# interface.net
KiCad netlist of a schematic drawn in Altium Designer
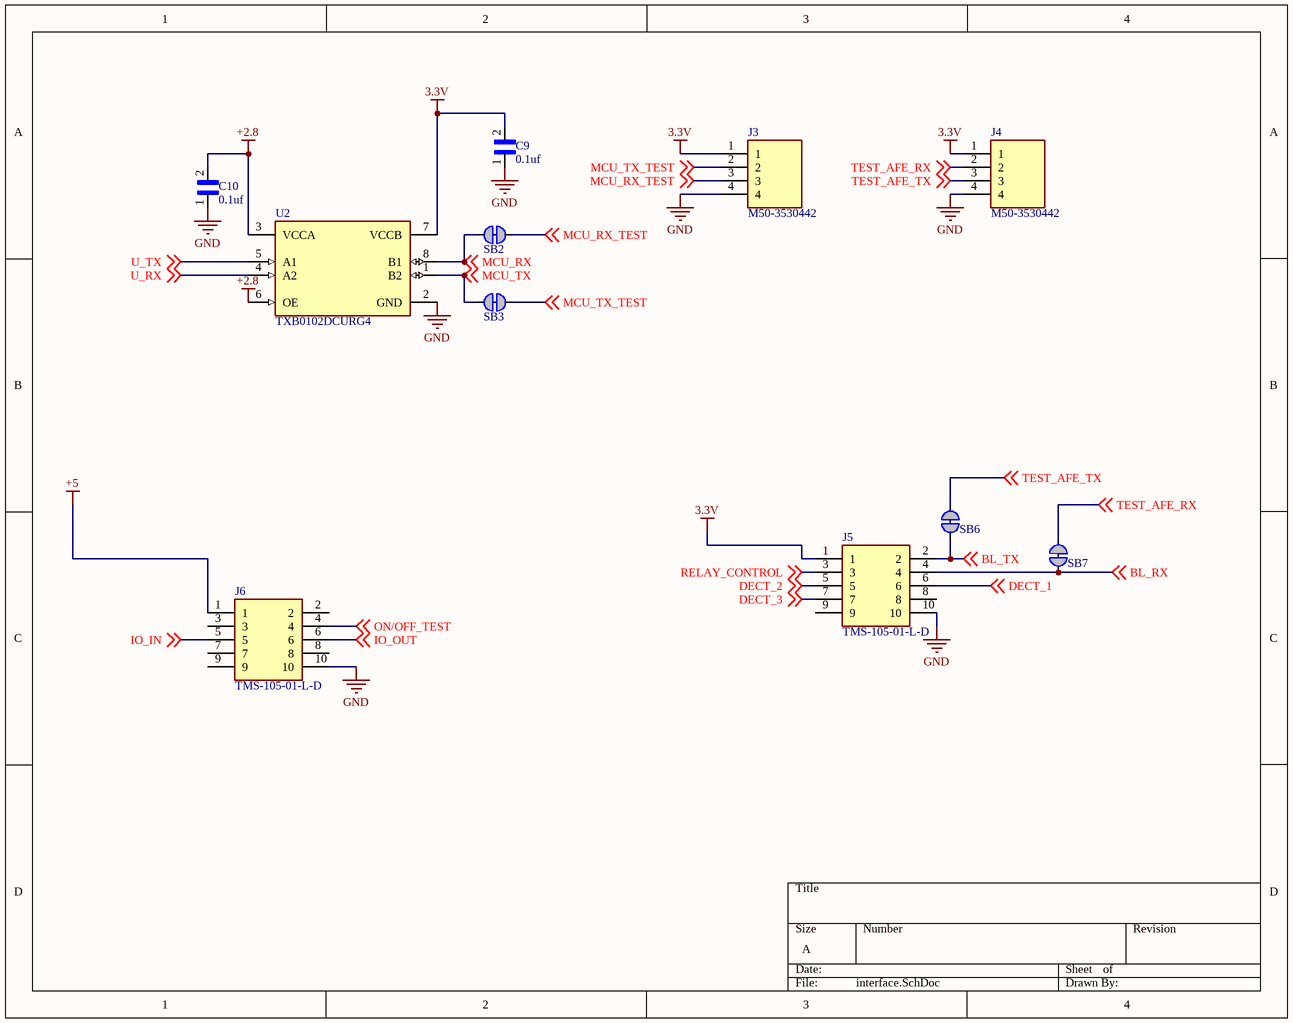
[diagram p0: interface.SchDoc]

(export (version "E")
  (design (tool "Eeschema 10.0.6"))
  (components
    (comp (ref "C9")
      (value "0.1uf")
      (footprint "CAPC1608X90N")
      (description "Cap Ceramic 0.1uF 25V Y5V -20% to 80% SMD 0603 85C T/R")
      (fields (field (name "MP") "06033G104ZAT4A") (field (name "MF") "{'manufacturer': u'AVX'}"))
      (libsource (lib "chargebot_alpha") (part "06033G104ZAT4A"))
    )
    (comp (ref "C10")
      (value "0.1uf")
      (footprint "CAPC1608X90N")
      (description "Cap Ceramic 0.1uF 25V Y5V -20% to 80% SMD 0603 85C T/R")
      (fields (field (name "MP") "06033G104ZAT4A") (field (name "MF") "{'manufacturer': u'AVX'}"))
      (libsource (lib "chargebot_alpha") (part "06033G104ZAT4A"))
    )
    (comp (ref "J3")
      (value "M50-3530442")
      (footprint "mouser_layout_lib:HDRV4W40P0X127_1X4_508X210X420P")
      (description "Connector")
      (fields (field (name "MOUSER PART NUMBER") "855-M50-3530442"))
      (libsource (lib "*") (part "M50-3530442"))
    )
    (comp (ref "J4")
      (value "M50-3530442")
      (footprint "mouser_layout_lib:HDRV4W40P0X127_1X4_508X210X420P")
      (description "Connector")
      (fields (field (name "MOUSER PART NUMBER") "855-M50-3530442"))
      (libsource (lib "*") (part "M50-3530442"))
    )
    (comp (ref "J5")
      (value "TMS-105-01-L-D")
      (footprint "mouser_layout_lib:HDRV10W51P254X127_2X5_635X498X838P")
      (description "Connector")
      (fields (field (name "MOUSER PART NUMBER") "200-TMS10501LD"))
      (libsource (lib "*") (part "TMS-105-01-L-D"))
    )
    (comp (ref "J6")
      (value "TMS-105-01-L-D")
      (footprint "mouser_layout_lib:HDRV10W51P254X127_2X5_635X498X838P")
      (description "Connector")
      (fields (field (name "MOUSER PART NUMBER") "200-TMS10501LD"))
      (libsource (lib "*") (part "TMS-105-01-L-D"))
    )
    (comp (ref "SB2")
      (value "Solderbridge")
      (footprint "SOLDERBRIDGE_SHORTED")
      (description "Shorted Solderbridge")
      (fields
        (field (name "PART NUMBER") "Solderbridge Shorted")
        (field (name "PUBLISHER") "Nordic Semiconductor")
      )
      (libsource (lib "apollo2-amaph1kk-kbr-brd") (part "SOLDERBRIDGE_SHORTED"))
    )
    (comp (ref "SB3")
      (value "Solderbridge")
      (footprint "SOLDERBRIDGE_SHORTED")
      (description "Shorted Solderbridge")
      (fields
        (field (name "PART NUMBER") "Solderbridge Shorted")
        (field (name "PUBLISHER") "Nordic Semiconductor")
      )
      (libsource (lib "apollo2-amaph1kk-kbr-brd") (part "SOLDERBRIDGE_SHORTED"))
    )
    (comp (ref "SB6")
      (value "Solderbridge")
      (footprint "SOLDERBRIDGE_SHORTED")
      (description "Shorted Solderbridge")
      (fields
        (field (name "PART NUMBER") "Solderbridge Shorted")
        (field (name "PUBLISHER") "Nordic Semiconductor")
      )
      (libsource (lib "apollo2-amaph1kk-kbr-brd") (part "SOLDERBRIDGE_SHORTED"))
    )
    (comp (ref "SB7")
      (value "Solderbridge")
      (footprint "SOLDERBRIDGE_SHORTED")
      (description "Shorted Solderbridge")
      (fields
        (field (name "PART NUMBER") "Solderbridge Shorted")
        (field (name "PUBLISHER") "Nordic Semiconductor")
      )
      (libsource (lib "apollo2-amaph1kk-kbr-brd") (part "SOLDERBRIDGE_SHORTED"))
    )
    (comp (ref "U2")
      (value "TXB0102DCURG4")
      (footprint "SOP50P310X90-8N")
      (description "IC TRNSLTR BIDIRECTIONAL US8")
      (libsource (lib "chargebot_alpha") (part "e5aacda1e23edf748dee3cec588ab45"))
    )
  )
  (nets
    (net (code "1") (name "+2.8") (class "Default")
      (node (ref "C10") (pin "2") (pinfunction "2_2") (pintype "passive"))
      (node (ref "U2") (pin "3") (pinfunction "VCCA_3") (pintype "passive"))
      (node (ref "U2") (pin "6") (pinfunction "OE_6") (pintype "input"))
    )
    (net (code "2") (name "+5") (class "Default")
      (node (ref "J6") (pin "1") (pinfunction "1_1") (pintype "passive"))
    )
    (net (code "3") (name "3.3V") (class "Default")
      (node (ref "C9") (pin "2") (pinfunction "2_2") (pintype "passive"))
      (node (ref "J3") (pin "1") (pinfunction "1_1") (pintype "passive"))
      (node (ref "J4") (pin "1") (pinfunction "1_1") (pintype "passive"))
      (node (ref "J5") (pin "1") (pinfunction "1_1") (pintype "passive"))
      (node (ref "U2") (pin "7") (pinfunction "VCCB_7") (pintype "passive"))
    )
    (net (code "4") (name "BL_RX") (class "Default")
      (node (ref "J5") (pin "4") (pinfunction "4_4") (pintype "passive"))
      (node (ref "SB7") (pin "2") (pinfunction "1_2") (pintype "passive"))
    )
    (net (code "5") (name "BL_TX") (class "Default")
      (node (ref "J5") (pin "2") (pinfunction "2_2") (pintype "passive"))
      (node (ref "SB6") (pin "1") (pinfunction "0_1") (pintype "passive"))
    )
    (net (code "6") (name "DECT_1") (class "Default")
      (node (ref "J5") (pin "6") (pinfunction "6_6") (pintype "passive"))
    )
    (net (code "7") (name "DECT_2") (class "Default")
      (node (ref "J5") (pin "5") (pinfunction "5_5") (pintype "passive"))
    )
    (net (code "8") (name "DECT_3") (class "Default")
      (node (ref "J5") (pin "7") (pinfunction "7_7") (pintype "passive"))
    )
    (net (code "9") (name "GND") (class "Default")
      (node (ref "C10") (pin "1") (pinfunction "1_1") (pintype "passive"))
      (node (ref "C9") (pin "1") (pinfunction "1_1") (pintype "passive"))
      (node (ref "J3") (pin "4") (pinfunction "4_4") (pintype "passive"))
      (node (ref "J4") (pin "4") (pinfunction "4_4") (pintype "passive"))
      (node (ref "J5") (pin "10") (pinfunction "10_10") (pintype "passive"))
      (node (ref "J6") (pin "10") (pinfunction "10_10") (pintype "passive"))
      (node (ref "U2") (pin "2") (pinfunction "GND_2") (pintype "power_in"))
    )
    (net (code "10") (name "IO_IN") (class "Default")
      (node (ref "J6") (pin "5") (pinfunction "5_5") (pintype "passive"))
    )
    (net (code "11") (name "IO_OUT") (class "Default")
      (node (ref "J6") (pin "6") (pinfunction "6_6") (pintype "passive"))
    )
    (net (code "12") (name "MCU_RX") (class "Default")
      (node (ref "SB2") (pin "2") (pinfunction "1_2") (pintype "passive"))
      (node (ref "U2") (pin "8") (pinfunction "B1_8") (pintype "bidirectional"))
    )
    (net (code "13") (name "MCU_RX_TEST") (class "Default")
      (node (ref "J3") (pin "3") (pinfunction "3_3") (pintype "passive"))
      (node (ref "SB2") (pin "1") (pinfunction "0_1") (pintype "passive"))
    )
    (net (code "14") (name "MCU_TX") (class "Default")
      (node (ref "SB3") (pin "2") (pinfunction "1_2") (pintype "passive"))
      (node (ref "U2") (pin "1") (pinfunction "B2_1") (pintype "bidirectional"))
    )
    (net (code "15") (name "MCU_TX_TEST") (class "Default")
      (node (ref "J3") (pin "2") (pinfunction "2_2") (pintype "passive"))
      (node (ref "SB3") (pin "1") (pinfunction "0_1") (pintype "passive"))
    )
    (net (code "16") (name "ON{slash}OFF_TEST") (class "Default")
      (node (ref "J6") (pin "4") (pinfunction "4_4") (pintype "passive"))
    )
    (net (code "17") (name "RELAY_CONTROL") (class "Default")
      (node (ref "J5") (pin "3") (pinfunction "3_3") (pintype "passive"))
    )
    (net (code "18") (name "TEST_AFE_RX") (class "Default")
      (node (ref "J4") (pin "2") (pinfunction "2_2") (pintype "passive"))
      (node (ref "SB7") (pin "1") (pinfunction "0_1") (pintype "passive"))
    )
    (net (code "19") (name "TEST_AFE_TX") (class "Default")
      (node (ref "J4") (pin "3") (pinfunction "3_3") (pintype "passive"))
      (node (ref "SB6") (pin "2") (pinfunction "1_2") (pintype "passive"))
    )
    (net (code "20") (name "U_RX") (class "Default")
      (node (ref "U2") (pin "4") (pinfunction "A2_4") (pintype "input"))
    )
    (net (code "21") (name "U_TX") (class "Default")
      (node (ref "U2") (pin "5") (pinfunction "A1_5") (pintype "input"))
    )
    (net (code "22") (name "unconnected-(J5-Pad8)") (class "Default")
      (node (ref "J5") (pin "8") (pinfunction "8_8") (pintype "passive"))
    )
    (net (code "23") (name "unconnected-(J5-Pad9)") (class "Default")
      (node (ref "J5") (pin "9") (pinfunction "9_9") (pintype "passive"))
    )
    (net (code "24") (name "unconnected-(J6-Pad2)") (class "Default")
      (node (ref "J6") (pin "2") (pinfunction "2_2") (pintype "passive"))
    )
    (net (code "25") (name "unconnected-(J6-Pad3)") (class "Default")
      (node (ref "J6") (pin "3") (pinfunction "3_3") (pintype "passive"))
    )
    (net (code "26") (name "unconnected-(J6-Pad7)") (class "Default")
      (node (ref "J6") (pin "7") (pinfunction "7_7") (pintype "passive"))
    )
    (net (code "27") (name "unconnected-(J6-Pad8)") (class "Default")
      (node (ref "J6") (pin "8") (pinfunction "8_8") (pintype "passive"))
    )
    (net (code "28") (name "unconnected-(J6-Pad9)") (class "Default")
      (node (ref "J6") (pin "9") (pinfunction "9_9") (pintype "passive"))
    )
  )
)
